# Own_Sensor_Measuring_Bridge_dev_v1_0_Fin.net
KiCad netlist of a schematic drawn in EAGLE
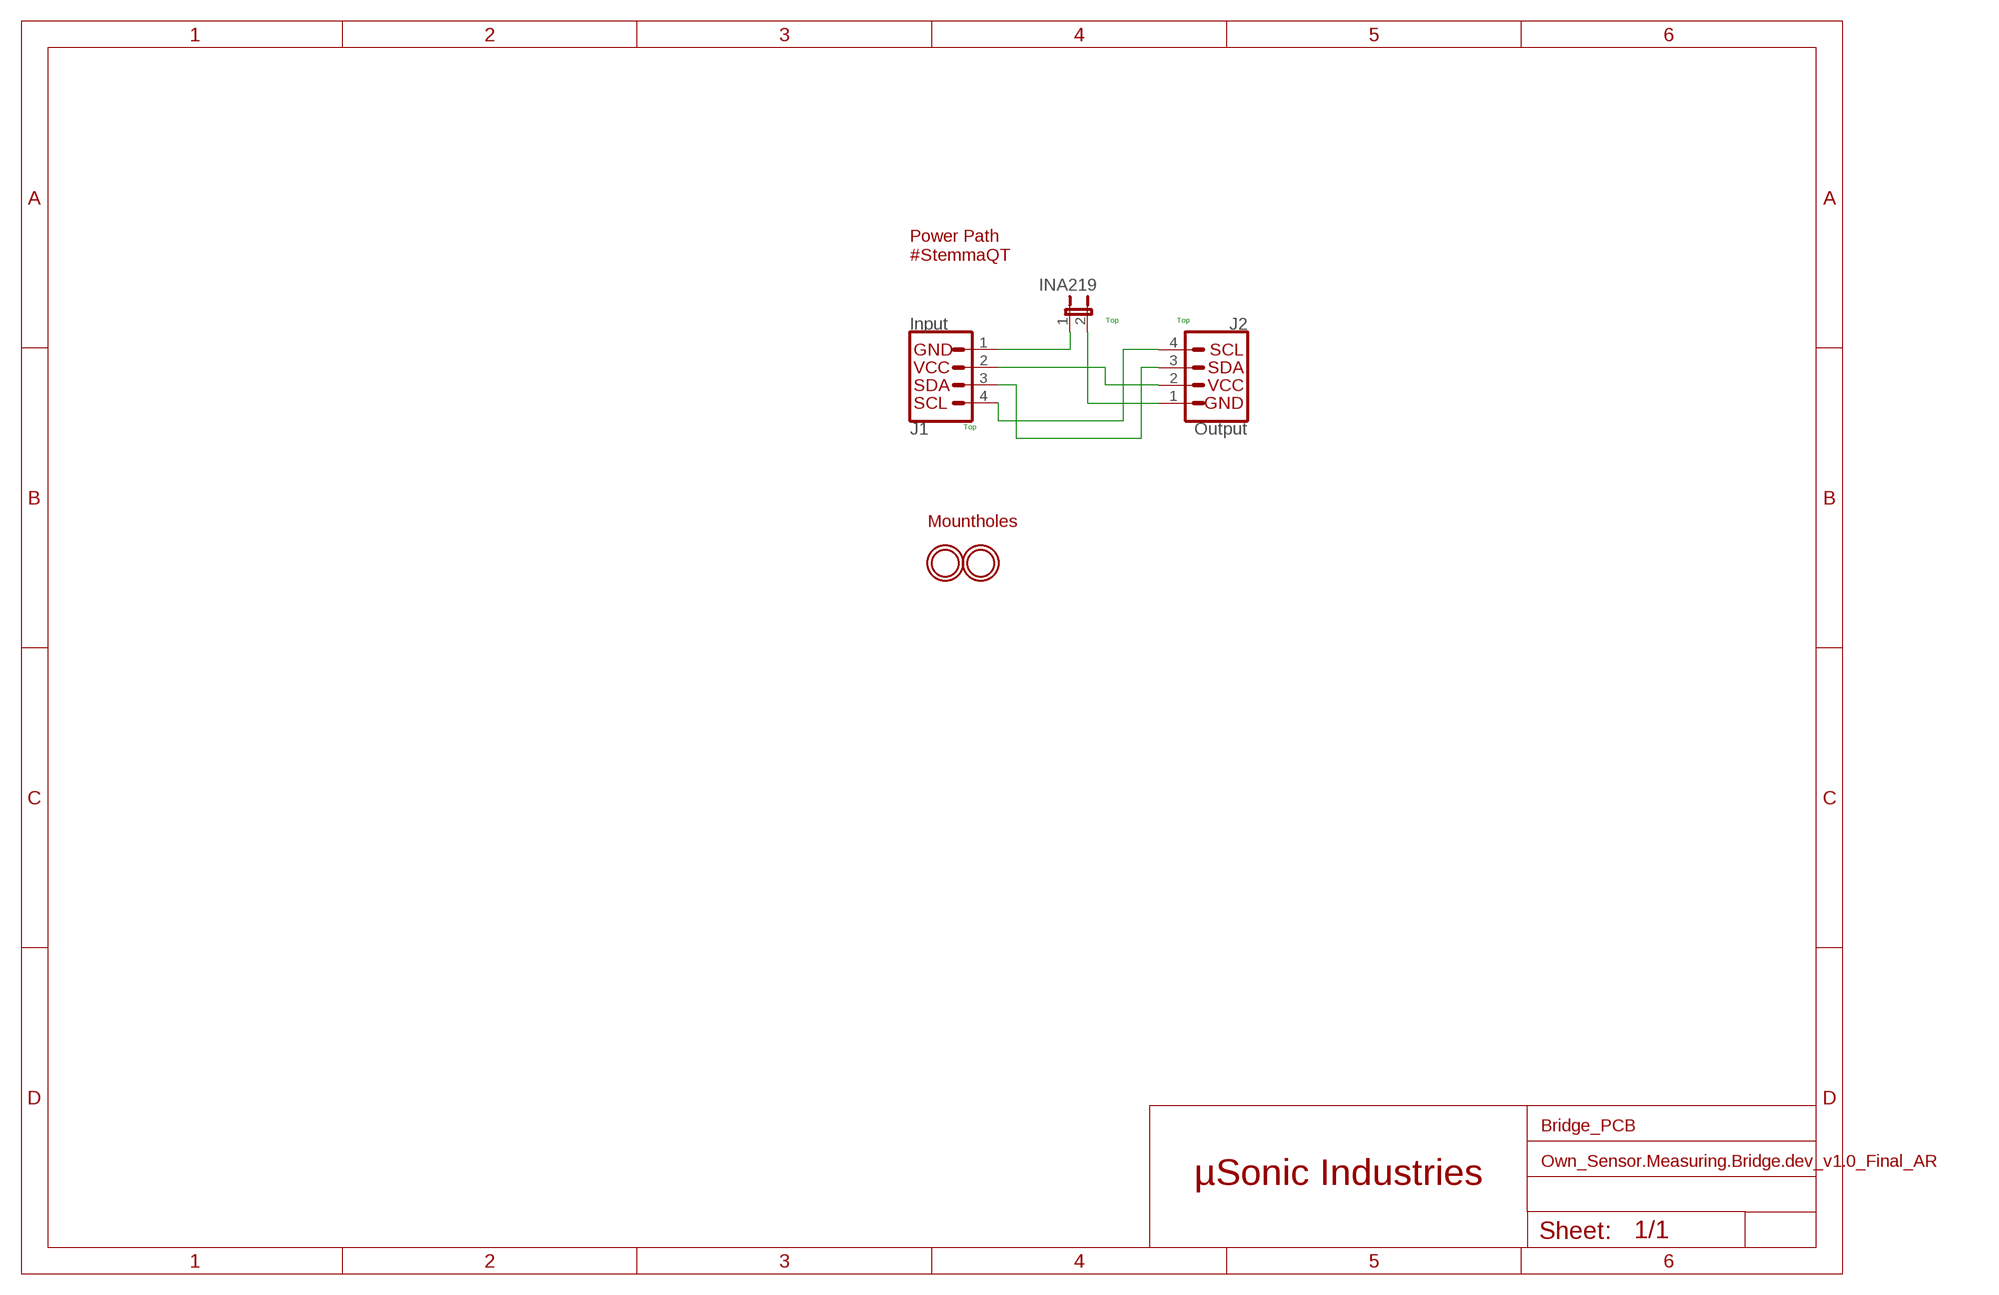
[diagram p0: schematic, sheet 1]

(export (version "E")
  (design (tool "Eeschema 10.0.6"))
  (components
    (comp (ref "INA219")
      (value "JP1E")
      (footprint "eagle-import:JP1")
      (libsource (lib "eagle-import") (part "JP1E"))
    )
    (comp (ref "J1")
      (value "Input")
      (footprint "eagle-import:JST04_1MM_RA")
      (libsource (lib "eagle-import") (part "I2C_STANDARDQWIIC"))
    )
    (comp (ref "J2")
      (value "Output")
      (footprint "eagle-import:JST04_1MM_RA")
      (libsource (lib "eagle-import") (part "I2C_STANDARDQWIIC"))
    )
    (comp (ref "U$18")
      (value "MOUNTINGHOLE2.5")
      (footprint "eagle-import:MOUNTINGHOLE_2.5_PLATED")
      (libsource (lib "eagle-import") (part "MOUNTINGHOLE2.5"))
    )
    (comp (ref "U$19")
      (value "MOUNTINGHOLE2.5")
      (footprint "eagle-import:MOUNTINGHOLE_2.5_PLATED")
      (libsource (lib "eagle-import") (part "MOUNTINGHOLE2.5"))
    )
  )
  (nets
    (net (code "1") (name "Net-(INA219-Pad1)") (class "Default")
      (node (ref "INA219") (pin "1") (pinfunction "1_1") (pintype "passive"))
      (node (ref "J1") (pin "1") (pinfunction "1_1") (pintype "power_in"))
    )
    (net (code "2") (name "Net-(INA219-Pad2)") (class "Default")
      (node (ref "INA219") (pin "2") (pinfunction "2_2") (pintype "passive"))
      (node (ref "J2") (pin "1") (pinfunction "1_1") (pintype "power_in"))
    )
    (net (code "3") (name "Net-(J1-Pad2)") (class "Default")
      (node (ref "J1") (pin "2") (pinfunction "2_2") (pintype "power_in"))
      (node (ref "J2") (pin "2") (pinfunction "2_2") (pintype "power_in"))
    )
    (net (code "4") (name "Net-(J1-Pad3)") (class "Default")
      (node (ref "J1") (pin "3") (pinfunction "3_3") (pintype "passive"))
      (node (ref "J2") (pin "3") (pinfunction "3_3") (pintype "passive"))
    )
    (net (code "5") (name "Net-(J1-Pad4)") (class "Default")
      (node (ref "J1") (pin "4") (pinfunction "4_4") (pintype "passive"))
      (node (ref "J2") (pin "4") (pinfunction "4_4") (pintype "passive"))
    )
  )
)
